# Versterker.net
KiCad netlist of a schematic drawn in Altium Designer
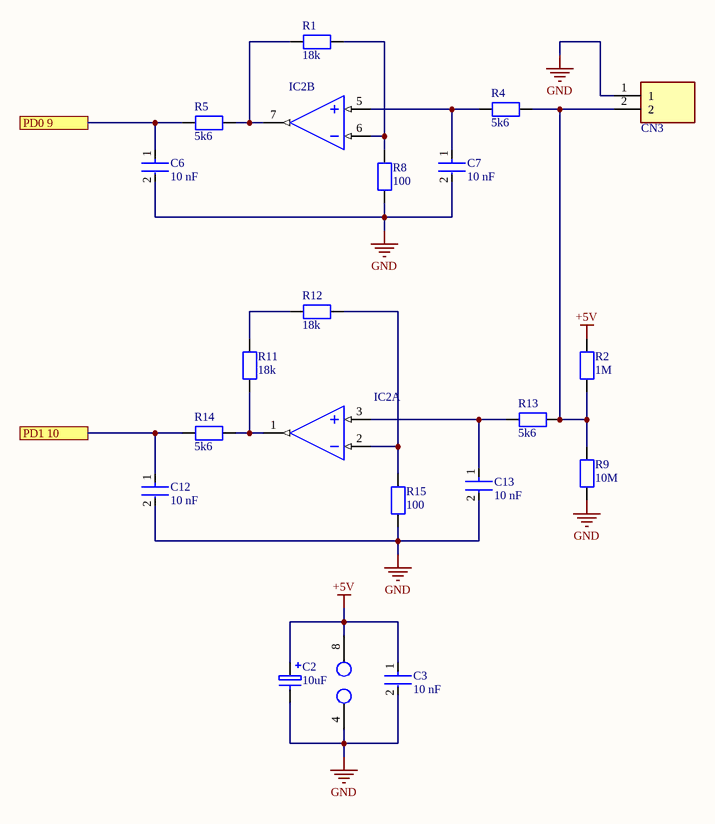
[diagram p0: Versterker.SchDoc]

(export (version "E")
  (design (tool "Eeschema 10.0.6"))
  (components
    (comp (ref "C2")
      (value "10uF")
      (footprint "Elco 100uF 25V")
      (fields
        (field (name "PART NUMBER") "02015A270JAT2A")
        (field (name "MANUFACTURER") "AVX Interconnect / Elco")
      )
      (libsource (lib "Schlib1") (part "Condensator Elco"))
    )
    (comp (ref "C3")
      (value "10 nF")
      (footprint "0805")
      (description "Chip Multilayer Ceramic Capacitors for General Purpose, 0805, 10uF, X5R, 15%, 10%, 25V")
      (fields (field (name "VOLTAGE") "25V") (field (name "TOLERANCE") "10%"))
      (libsource (lib "Schlib1") (part "Condensator 0805"))
    )
    (comp (ref "C6")
      (value "10 nF")
      (footprint "0805")
      (description "Chip Multilayer Ceramic Capacitors for General Purpose, 0805, 10uF, X5R, 15%, 10%, 25V")
      (fields (field (name "VOLTAGE") "25V") (field (name "TOLERANCE") "10%"))
      (libsource (lib "Schlib1") (part "Condensator 0805"))
    )
    (comp (ref "C7")
      (value "10 nF")
      (footprint "0805")
      (description "Chip Multilayer Ceramic Capacitors for General Purpose, 0805, 10uF, X5R, 15%, 10%, 25V")
      (fields (field (name "VOLTAGE") "25V") (field (name "TOLERANCE") "10%"))
      (libsource (lib "Schlib1") (part "Condensator 0805"))
    )
    (comp (ref "C12")
      (value "10 nF")
      (footprint "0805")
      (description "Chip Multilayer Ceramic Capacitors for General Purpose, 0805, 10uF, X5R, 15%, 10%, 25V")
      (fields (field (name "VOLTAGE") "25V") (field (name "TOLERANCE") "10%"))
      (libsource (lib "Schlib1") (part "Condensator 0805"))
    )
    (comp (ref "C13")
      (value "10 nF")
      (footprint "0805")
      (description "Chip Multilayer Ceramic Capacitors for General Purpose, 0805, 10uF, X5R, 15%, 10%, 25V")
      (fields (field (name "VOLTAGE") "25V") (field (name "TOLERANCE") "10%"))
      (libsource (lib "Schlib1") (part "Condensator 0805"))
    )
    (comp (ref "CN3")
      (value "282836-2")
      (footprint "SamacSys:2828362")
      (description "Connector")
      (libsource (lib "Schlib1") (part "Schroefconnector 2 Pin R"))
    )
    (comp (ref "IC2")
      (value "MCP6002-I/P")
      (footprint "Opamp")
      (description "AMP-OPA-MCP6002-IL8")
      (libsource (lib "Schlib1") (part "Opamp"))
    )
    (comp (ref "R1")
      (value "18k")
      (footprint "0805")
      (fields (field (name "MANUFACTURER") "Vishay Dale") (field (name "PART NUMBER") "CRCW08050000Z0EA"))
      (libsource (lib "Schlib1") (part "Resistor 0805"))
    )
    (comp (ref "R2")
      (value "1M")
      (footprint "0805")
      (fields (field (name "MANUFACTURER") "Vishay Dale") (field (name "PART NUMBER") "CRCW08050000Z0EA"))
      (libsource (lib "Schlib1") (part "Resistor 0805"))
    )
    (comp (ref "R4")
      (value "5k6")
      (footprint "0805")
      (fields (field (name "MANUFACTURER") "Vishay Dale") (field (name "PART NUMBER") "CRCW08050000Z0EA"))
      (libsource (lib "Schlib1") (part "Resistor 0805"))
    )
    (comp (ref "R5")
      (value "5k6")
      (footprint "0805")
      (fields (field (name "MANUFACTURER") "Vishay Dale") (field (name "PART NUMBER") "CRCW08050000Z0EA"))
      (libsource (lib "Schlib1") (part "Resistor 0805"))
    )
    (comp (ref "R8")
      (value "100")
      (footprint "0805")
      (fields (field (name "MANUFACTURER") "Vishay Dale") (field (name "PART NUMBER") "CRCW08050000Z0EA"))
      (libsource (lib "Schlib1") (part "Resistor 0805"))
    )
    (comp (ref "R9")
      (value "10M")
      (footprint "0805")
      (fields (field (name "MANUFACTURER") "Vishay Dale") (field (name "PART NUMBER") "CRCW08050000Z0EA"))
      (libsource (lib "Schlib1") (part "Resistor 0805"))
    )
    (comp (ref "R11")
      (value "18k")
      (footprint "0805")
      (fields (field (name "MANUFACTURER") "Vishay Dale") (field (name "PART NUMBER") "CRCW08050000Z0EA"))
      (libsource (lib "Schlib1") (part "Resistor 0805"))
    )
    (comp (ref "R12")
      (value "18k")
      (footprint "0805")
      (fields (field (name "MANUFACTURER") "Vishay Dale") (field (name "PART NUMBER") "CRCW08050000Z0EA"))
      (libsource (lib "Schlib1") (part "Resistor 0805"))
    )
    (comp (ref "R13")
      (value "5k6")
      (footprint "0805")
      (fields (field (name "MANUFACTURER") "Vishay Dale") (field (name "PART NUMBER") "CRCW08050000Z0EA"))
      (libsource (lib "Schlib1") (part "Resistor 0805"))
    )
    (comp (ref "R14")
      (value "5k6")
      (footprint "0805")
      (fields (field (name "MANUFACTURER") "Vishay Dale") (field (name "PART NUMBER") "CRCW08050000Z0EA"))
      (libsource (lib "Schlib1") (part "Resistor 0805"))
    )
    (comp (ref "R15")
      (value "100")
      (footprint "0805")
      (fields (field (name "MANUFACTURER") "Vishay Dale") (field (name "PART NUMBER") "CRCW08050000Z0EA"))
      (libsource (lib "Schlib1") (part "Resistor 0805"))
    )
  )
  (nets
    (net (code "1") (name "+5V") (class "Default")
      (node (ref "C2") (pin "1") (pinfunction "1_1") (pintype "passive"))
      (node (ref "C3") (pin "1") (pinfunction "1_1") (pintype "passive"))
      (node (ref "IC2") (pin "8") (pintype "power_in"))
      (node (ref "R2") (pin "2") (pinfunction "2_2") (pintype "passive"))
    )
    (net (code "2") (name "/PD0 9") (class "Default")
      (node (ref "C6") (pin "1") (pinfunction "1_1") (pintype "passive"))
      (node (ref "R5") (pin "1") (pinfunction "1_1") (pintype "passive"))
    )
    (net (code "3") (name "/PD1 10") (class "Default")
      (node (ref "C12") (pin "1") (pinfunction "1_1") (pintype "passive"))
      (node (ref "R14") (pin "1") (pinfunction "1_1") (pintype "passive"))
    )
    (net (code "4") (name "GND") (class "Default")
      (node (ref "C12") (pin "2") (pinfunction "2_2") (pintype "passive"))
      (node (ref "C13") (pin "2") (pinfunction "2_2") (pintype "passive"))
      (node (ref "C2") (pin "2") (pinfunction "2_2") (pintype "passive"))
      (node (ref "C3") (pin "2") (pinfunction "2_2") (pintype "passive"))
      (node (ref "C6") (pin "2") (pinfunction "2_2") (pintype "passive"))
      (node (ref "C7") (pin "2") (pinfunction "2_2") (pintype "passive"))
      (node (ref "CN3") (pin "1") (pinfunction "1_1") (pintype "passive"))
      (node (ref "IC2") (pin "4") (pintype "power_in"))
      (node (ref "R15") (pin "2") (pinfunction "2_2") (pintype "passive"))
      (node (ref "R8") (pin "1") (pinfunction "1_1") (pintype "passive"))
      (node (ref "R9") (pin "1") (pinfunction "1_1") (pintype "passive"))
    )
    (net (code "5") (name "Net-(C7-Pad1)") (class "Default")
      (node (ref "C7") (pin "1") (pinfunction "1_1") (pintype "passive"))
      (node (ref "IC2") (pin "5") (pintype "input"))
      (node (ref "R4") (pin "1") (pinfunction "1_1") (pintype "passive"))
    )
    (net (code "6") (name "Net-(C13-Pad1)") (class "Default")
      (node (ref "C13") (pin "1") (pinfunction "1_1") (pintype "passive"))
      (node (ref "IC2") (pin "3") (pintype "input"))
      (node (ref "R13") (pin "1") (pinfunction "1_1") (pintype "passive"))
    )
    (net (code "7") (name "Net-(CN3-Pad2)") (class "Default")
      (node (ref "CN3") (pin "2") (pinfunction "2_2") (pintype "passive"))
      (node (ref "R13") (pin "2") (pinfunction "2_2") (pintype "passive"))
      (node (ref "R2") (pin "1") (pinfunction "1_1") (pintype "passive"))
      (node (ref "R4") (pin "2") (pinfunction "2_2") (pintype "passive"))
      (node (ref "R9") (pin "2") (pinfunction "2_2") (pintype "passive"))
    )
    (net (code "8") (name "Net-(IC2-Pad1)") (class "Default")
      (node (ref "IC2") (pin "1") (pintype "output"))
      (node (ref "R11") (pin "2") (pinfunction "2_2") (pintype "passive"))
      (node (ref "R14") (pin "2") (pinfunction "2_2") (pintype "passive"))
    )
    (net (code "9") (name "Net-(IC2-Pad2)") (class "Default")
      (node (ref "IC2") (pin "2") (pintype "input"))
      (node (ref "R12") (pin "2") (pinfunction "2_2") (pintype "passive"))
      (node (ref "R15") (pin "1") (pinfunction "1_1") (pintype "passive"))
    )
    (net (code "10") (name "Net-(IC2-Pad6)") (class "Default")
      (node (ref "IC2") (pin "6") (pintype "input"))
      (node (ref "R1") (pin "2") (pinfunction "2_2") (pintype "passive"))
      (node (ref "R8") (pin "2") (pinfunction "2_2") (pintype "passive"))
    )
    (net (code "11") (name "Net-(IC2-Pad7)") (class "Default")
      (node (ref "IC2") (pin "7") (pintype "output"))
      (node (ref "R1") (pin "1") (pinfunction "1_1") (pintype "passive"))
      (node (ref "R5") (pin "2") (pinfunction "2_2") (pintype "passive"))
    )
    (net (code "12") (name "Net-(R11-Pad1)") (class "Default")
      (node (ref "R11") (pin "1") (pinfunction "1_1") (pintype "passive"))
      (node (ref "R12") (pin "1") (pinfunction "1_1") (pintype "passive"))
    )
  )
)
